# RunnersHighEA_HALL.net
KiCad netlist of a schematic drawn in EAGLE
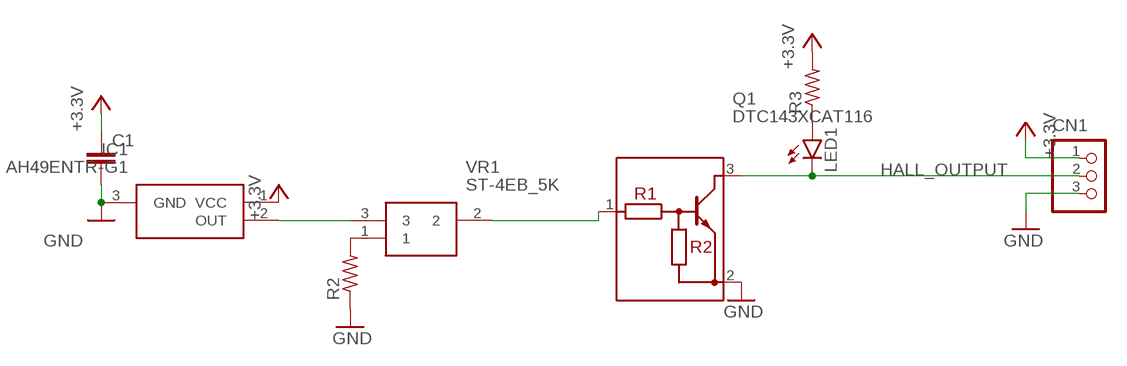
[diagram p0: schematic, sheet 1]

(export (version "E")
  (design (tool "Eeschema 10.0.6"))
  (components
    (comp (ref "C1")
      (value "C-EUC0603")
      (footprint "eagle-import:C0603")
      (libsource (lib "eagle-import") (part "C-EUC0603"))
    )
    (comp (ref "CN1")
      (value "S3B-PH-SM4-TB")
      (footprint "eagle-import:S3B-PH-SM4-TB")
      (libsource (lib "eagle-import") (part "S3B-PH-SM4-TB"))
    )
    (comp (ref "IC1")
      (value "AH49ENTR-G1")
      (footprint "eagle-import:SOT95P280X145-3N")
      (fields
        (field (name "MOUSER_PART_NUMBER") "621-AH49ENTR-G1")
        (field (name "RS_PART_NUMBER") "9210332P")
      )
      (libsource (lib "eagle-import") (part "AH49ENTR-G1"))
    )
    (comp (ref "LED1")
      (value "LEDCHIP-LED0603")
      (footprint "eagle-import:CHIP-LED0603")
      (libsource (lib "eagle-import") (part "LEDCHIP-LED0603"))
    )
    (comp (ref "Q1")
      (value "DTC143XCAT116")
      (footprint "eagle-import:SOT85P240X115-3N")
      (libsource (lib "eagle-import") (part "DTC143XCAT116"))
    )
    (comp (ref "R2")
      (value "R-US_R0603")
      (footprint "eagle-import:R0603")
      (libsource (lib "eagle-import") (part "R-US_R0603"))
    )
    (comp (ref "R3")
      (value "R-US_R0603")
      (footprint "eagle-import:R0603")
      (libsource (lib "eagle-import") (part "R-US_R0603"))
    )
    (comp (ref "VR1")
      (value "ST-4EB_5K")
      (footprint "eagle-import:ST-4EB")
      (fields (field (name "MANUFACTURER_PART_NUMBER") "ST-4EB 5k"))
      (libsource (lib "eagle-import") (part "ST-4EB_5K"))
    )
  )
  (nets
    (net (code "1") (name "+3.3V") (class "Default")
      (node (ref "C1") (pin "1") (pinfunction "1_1") (pintype "passive"))
      (node (ref "CN1") (pin "1") (pinfunction "1_1") (pintype "passive"))
      (node (ref "IC1") (pin "1") (pinfunction "VCC_1") (pintype "bidirectional"))
      (node (ref "R3") (pin "2") (pinfunction "2_2") (pintype "passive"))
    )
    (net (code "2") (name "/HALL_OUTPUT") (class "Default")
      (node (ref "CN1") (pin "2") (pinfunction "2_2") (pintype "passive"))
      (node (ref "LED1") (pin "C") (pinfunction "C_C") (pintype "passive"))
      (node (ref "Q1") (pin "3") (pinfunction "C_3") (pintype "bidirectional"))
    )
    (net (code "3") (name "GND") (class "Default")
      (node (ref "C1") (pin "2") (pinfunction "2_2") (pintype "passive"))
      (node (ref "CN1") (pin "3") (pinfunction "3_3") (pintype "passive"))
      (node (ref "IC1") (pin "3") (pinfunction "GND_3") (pintype "bidirectional"))
      (node (ref "Q1") (pin "2") (pinfunction "E_2") (pintype "bidirectional"))
      (node (ref "R2") (pin "1") (pinfunction "1_1") (pintype "passive"))
    )
    (net (code "4") (name "Net-(IC1-OUT)") (class "Default")
      (node (ref "IC1") (pin "2") (pinfunction "OUT_2") (pintype "bidirectional"))
      (node (ref "VR1") (pin "3") (pinfunction "3_3") (pintype "bidirectional"))
    )
    (net (code "5") (name "Net-(LED1-PadA)") (class "Default")
      (node (ref "LED1") (pin "A") (pinfunction "A_A") (pintype "passive"))
      (node (ref "R3") (pin "1") (pinfunction "1_1") (pintype "passive"))
    )
    (net (code "6") (name "Net-(Q1-B)") (class "Default")
      (node (ref "Q1") (pin "1") (pinfunction "B_1") (pintype "bidirectional"))
      (node (ref "VR1") (pin "2") (pinfunction "2_2") (pintype "bidirectional"))
    )
    (net (code "7") (name "Net-(R2-Pad2)") (class "Default")
      (node (ref "R2") (pin "2") (pinfunction "2_2") (pintype "passive"))
      (node (ref "VR1") (pin "1") (pinfunction "1_1") (pintype "bidirectional"))
    )
  )
)
